# hub.net
KiCad netlist of a schematic drawn in EAGLE
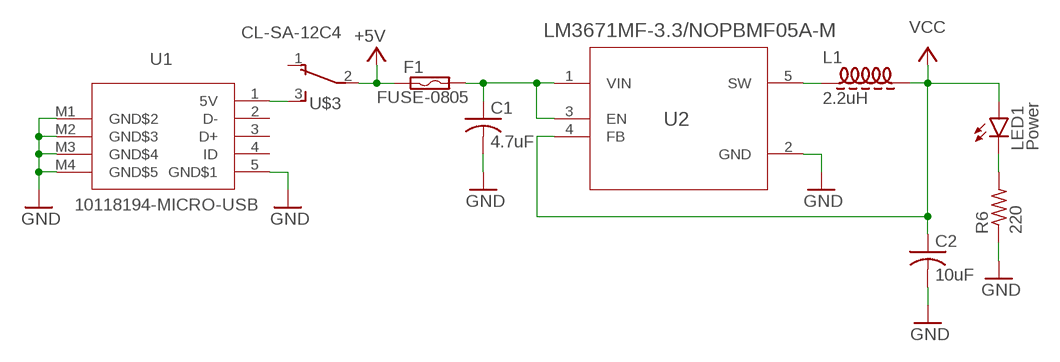
[diagram p0: schematic, sheet 1]
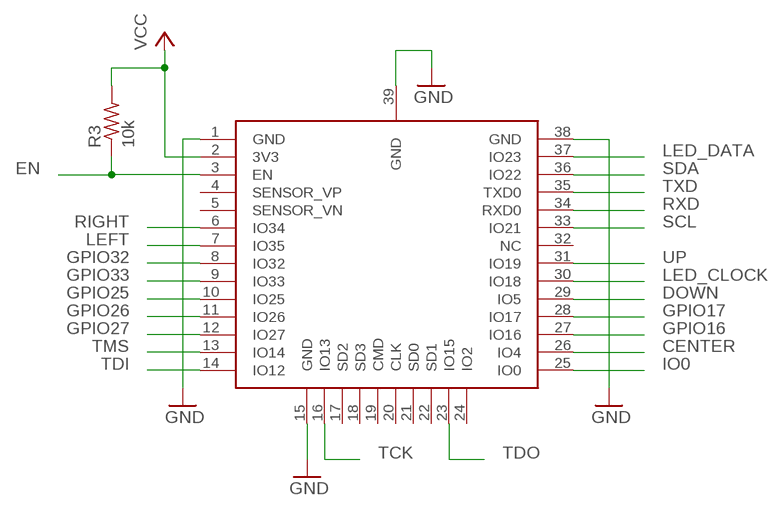
[diagram p1: schematic, sheet 2]
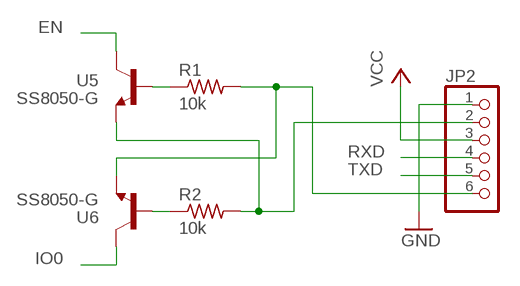
[diagram p2: schematic, sheet 3]
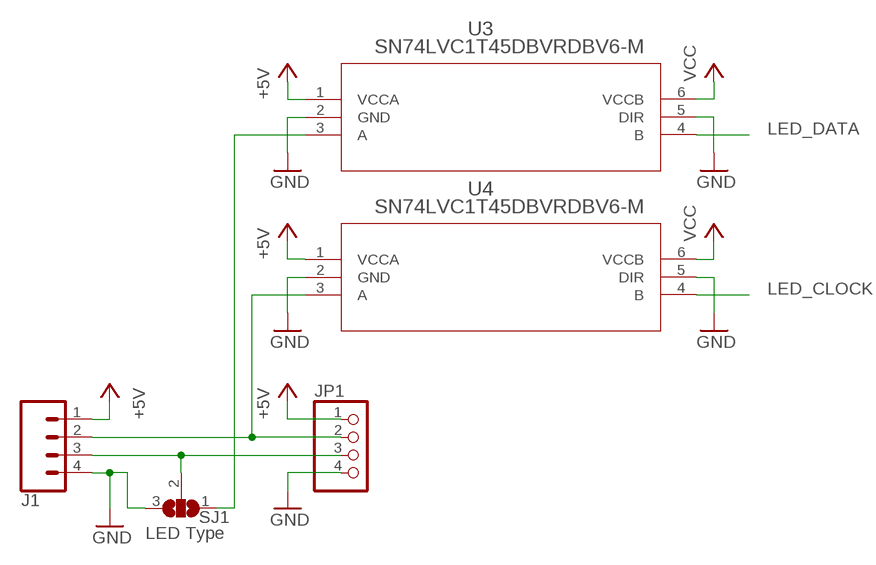
[diagram p3: schematic, sheet 4]
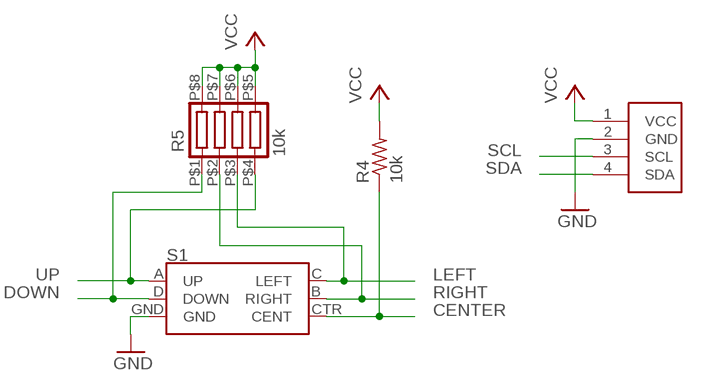
[diagram p4: schematic, sheet 5]
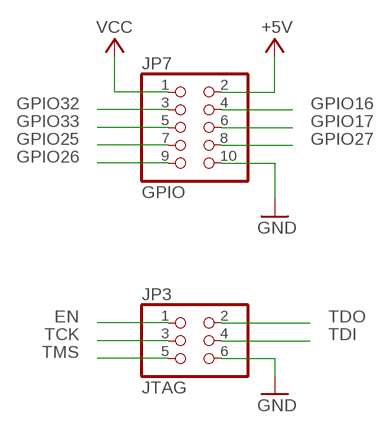
[diagram p5: schematic, sheet 6]

(export (version "E")
  (design (tool "Eeschema 10.0.6"))
  (components
    (comp (ref "R3")
      (value "10k")
      (footprint "eagle-import:R0805")
      (libsource (lib "eagle-import") (part "R-US_R0805"))
    )
    (comp (ref "U$2")
      (value "ESP32-WROOM-32D")
      (footprint "eagle-import:ESP32-WROOM-32D")
      (libsource (lib "eagle-import") (part "ESP32-WROOM-32D"))
    )
    (comp (ref "C1")
      (value "4.7uF")
      (footprint "eagle-import:C0805")
      (libsource (lib "eagle-import") (part "C-USC0805"))
    )
    (comp (ref "C2")
      (value "10uF")
      (footprint "eagle-import:C0805")
      (libsource (lib "eagle-import") (part "C-USC0805"))
    )
    (comp (ref "F1")
      (value "FUSE-0805")
      (footprint "eagle-import:R0805")
      (libsource (lib "eagle-import") (part "FUSE-0805"))
    )
    (comp (ref "L1")
      (value "2.2uH")
      (footprint "eagle-import:R0805")
      (libsource (lib "eagle-import") (part "IND-0805"))
    )
    (comp (ref "LED1")
      (value "Power")
      (footprint "eagle-import:CHIPLED_0805")
      (libsource (lib "eagle-import") (part "LEDCHIPLED_0805"))
    )
    (comp (ref "R6")
      (value "220")
      (footprint "eagle-import:R0805")
      (libsource (lib "eagle-import") (part "R-US_R0805"))
    )
    (comp (ref "U$3")
      (value "CL-SA-12C4")
      (footprint "eagle-import:CL-SA-12C4")
      (libsource (lib "eagle-import") (part "CL-SA-12C4"))
    )
    (comp (ref "U1")
      (value "10118194-MICRO-USB")
      (footprint "eagle-import:10118194-MICRO-USB")
      (libsource (lib "eagle-import") (part "10118194-MICRO-USB"))
    )
    (comp (ref "U2")
      (value "LM3671MF-3.3/NOPBMF05A-M")
      (footprint "eagle-import:MF05A-M")
      (fields (field (name "MANUFACTURER_PART_NUMBER") "LM3671MF3.3NOPB"))
      (libsource (lib "eagle-import") (part "LM3671MF-3.3/NOPBMF05A-M"))
    )
    (comp (ref "JP3")
      (value "JTAG")
      (footprint "eagle-import:2X03")
      (libsource (lib "eagle-import") (part "PINHD-2X3"))
    )
    (comp (ref "JP7")
      (value "GPIO")
      (footprint "eagle-import:2X05")
      (libsource (lib "eagle-import") (part "PINHD-2X5"))
    )
    (comp (ref "J1")
      (value "CONN_04SCREW")
      (footprint "eagle-import:SCREWTERMINAL-3.5MM-4")
      (libsource (lib "eagle-import") (part "CONN_04SCREW"))
    )
    (comp (ref "JP1")
      (value "PINHD-1X4")
      (footprint "eagle-import:1X04")
      (libsource (lib "eagle-import") (part "PINHD-1X4"))
    )
    (comp (ref "SJ1")
      (value "LED Type")
      (footprint "eagle-import:SJ_2")
      (libsource (lib "eagle-import") (part "SJ2W"))
    )
    (comp (ref "U3")
      (value "SN74LVC1T45DBVRDBV6-M")
      (footprint "eagle-import:DBV6-M")
      (fields (field (name "MANUFACTURER_PART_NUMBER") "SN74LVC1T45DBVR"))
      (libsource (lib "eagle-import") (part "SN74LVC1T45DBVRDBV6-M"))
    )
    (comp (ref "U4")
      (value "SN74LVC1T45DBVRDBV6-M")
      (footprint "eagle-import:DBV6-M")
      (fields (field (name "MANUFACTURER_PART_NUMBER") "SN74LVC1T45DBVR"))
      (libsource (lib "eagle-import") (part "SN74LVC1T45DBVRDBV6-M"))
    )
    (comp (ref "JP2")
      (value "FTDI")
      (footprint "eagle-import:1X06")
      (libsource (lib "eagle-import") (part "PINHD-1X6"))
    )
    (comp (ref "R1")
      (value "10k")
      (footprint "eagle-import:R0805")
      (libsource (lib "eagle-import") (part "R-US_R0805"))
    )
    (comp (ref "R2")
      (value "10k")
      (footprint "eagle-import:R0805")
      (libsource (lib "eagle-import") (part "R-US_R0805"))
    )
    (comp (ref "U5")
      (value "SS8050-G")
      (footprint "eagle-import:SC-59")
      (libsource (lib "eagle-import") (part "SS8050-G"))
    )
    (comp (ref "U6")
      (value "SS8050-G")
      (footprint "eagle-import:SC-59")
      (libsource (lib "eagle-import") (part "SS8050-G"))
    )
    (comp (ref "R4")
      (value "10k")
      (footprint "eagle-import:R0805")
      (libsource (lib "eagle-import") (part "R-US_R0805"))
    )
    (comp (ref "R5")
      (value "10k")
      (footprint "eagle-import:2012-4N-CONCAVE")
      (libsource (lib "eagle-import") (part "744C083"))
    )
    (comp (ref "S1")
      (value "JOYSTICK_MINI")
      (footprint "eagle-import:JOYSTICK_MINI")
      (libsource (lib "eagle-import") (part "JOYSTICK_MINI"))
    )
    (comp (ref "U$5")
      (value "SSD1306-OLED")
      (footprint "eagle-import:SSD1306-OLED")
      (libsource (lib "eagle-import") (part "SSD1306-OLED"))
    )
  )
  (nets
    (net (code "1") (name "+5V") (class "Default")
      (node (ref "F1") (pin "1") (pinfunction "1_1") (pintype "passive"))
      (node (ref "J1") (pin "1") (pinfunction "1_1") (pintype "passive"))
      (node (ref "JP1") (pin "1") (pinfunction "1_1") (pintype "passive"))
      (node (ref "JP7") (pin "2") (pinfunction "2_2") (pintype "passive"))
      (node (ref "U$3") (pin "2") (pinfunction "2_2") (pintype "passive"))
      (node (ref "U3") (pin "1") (pinfunction "VCCA_1") (pintype "power_in"))
      (node (ref "U4") (pin "1") (pinfunction "VCCA_1") (pintype "power_in"))
    )
    (net (code "2") (name "CENTER") (class "Default")
      (node (ref "R4") (pin "1") (pinfunction "1_1") (pintype "passive"))
      (node (ref "S1") (pin "CTR") (pinfunction "CENT_CTR") (pintype "bidirectional"))
      (node (ref "U$2") (pin "26") (pinfunction "IO4_26") (pintype "bidirectional"))
    )
    (net (code "3") (name "DOWN") (class "Default")
      (node (ref "R5") (pin "P$1") (pinfunction "1_P$1") (pintype "passive"))
      (node (ref "S1") (pin "D") (pinfunction "DOWN_D") (pintype "bidirectional"))
      (node (ref "U$2") (pin "29") (pinfunction "IO5_29") (pintype "passive"))
    )
    (net (code "4") (name "EN") (class "Default")
      (node (ref "JP3") (pin "1") (pinfunction "1_1") (pintype "passive"))
      (node (ref "R3") (pin "1") (pinfunction "1_1") (pintype "passive"))
      (node (ref "U$2") (pin "3") (pinfunction "EN_3") (pintype "passive"))
      (node (ref "U5") (pin "3") (pinfunction "C_3") (pintype "passive"))
    )
    (net (code "5") (name "GND") (class "Default")
      (node (ref "C1") (pin "2") (pinfunction "2_2") (pintype "passive"))
      (node (ref "C2") (pin "2") (pinfunction "2_2") (pintype "passive"))
      (node (ref "J1") (pin "4") (pinfunction "4_4") (pintype "passive"))
      (node (ref "JP1") (pin "4") (pinfunction "4_4") (pintype "passive"))
      (node (ref "JP2") (pin "1") (pinfunction "1_1") (pintype "passive"))
      (node (ref "JP3") (pin "6") (pinfunction "6_6") (pintype "passive"))
      (node (ref "JP7") (pin "10") (pinfunction "10_10") (pintype "passive"))
      (node (ref "R6") (pin "1") (pinfunction "1_1") (pintype "passive"))
      (node (ref "S1") (pin "GND") (pinfunction "GND_GND") (pintype "bidirectional"))
      (node (ref "SJ1") (pin "3") (pinfunction "3_3") (pintype "passive"))
      (node (ref "U$2") (pin "1") (pinfunction "GND_1") (pintype "passive"))
      (node (ref "U$2") (pin "15") (pinfunction "GND_15") (pintype "passive"))
      (node (ref "U$2") (pin "38") (pinfunction "GND_38") (pintype "passive"))
      (node (ref "U$2") (pin "39") (pinfunction "GND_39") (pintype "bidirectional"))
      (node (ref "U$5") (pin "2") (pinfunction "GND_2") (pintype "power_in"))
      (node (ref "U1") (pin "5") (pinfunction "GND$1_5") (pintype "bidirectional"))
      (node (ref "U1") (pin "M1") (pinfunction "GND$2_M1") (pintype "passive"))
      (node (ref "U1") (pin "M2") (pinfunction "GND$3_M2") (pintype "passive"))
      (node (ref "U1") (pin "M3") (pinfunction "GND$4_M3") (pintype "passive"))
      (node (ref "U1") (pin "M4") (pinfunction "GND$5_M4") (pintype "passive"))
      (node (ref "U2") (pin "2") (pinfunction "GND_2") (pintype "passive"))
      (node (ref "U3") (pin "2") (pinfunction "GND_2") (pintype "power_in"))
      (node (ref "U3") (pin "5") (pinfunction "DIR_5") (pintype "input"))
      (node (ref "U4") (pin "2") (pinfunction "GND_2") (pintype "power_in"))
      (node (ref "U4") (pin "5") (pinfunction "DIR_5") (pintype "input"))
    )
    (net (code "6") (name "GPIO16") (class "Default")
      (node (ref "JP7") (pin "4") (pinfunction "4_4") (pintype "passive"))
      (node (ref "U$2") (pin "27") (pinfunction "IO16_27") (pintype "bidirectional"))
    )
    (net (code "7") (name "GPIO17") (class "Default")
      (node (ref "JP7") (pin "6") (pinfunction "6_6") (pintype "passive"))
      (node (ref "U$2") (pin "28") (pinfunction "IO17_28") (pintype "passive"))
    )
    (net (code "8") (name "GPIO25") (class "Default")
      (node (ref "JP7") (pin "7") (pinfunction "7_7") (pintype "passive"))
      (node (ref "U$2") (pin "10") (pinfunction "IO25_10") (pintype "passive"))
    )
    (net (code "9") (name "GPIO26") (class "Default")
      (node (ref "JP7") (pin "9") (pinfunction "9_9") (pintype "passive"))
      (node (ref "U$2") (pin "11") (pinfunction "IO26_11") (pintype "passive"))
    )
    (net (code "10") (name "GPIO27") (class "Default")
      (node (ref "JP7") (pin "8") (pinfunction "8_8") (pintype "passive"))
      (node (ref "U$2") (pin "12") (pinfunction "IO27_12") (pintype "bidirectional"))
    )
    (net (code "11") (name "GPIO32") (class "Default")
      (node (ref "JP7") (pin "3") (pinfunction "3_3") (pintype "passive"))
      (node (ref "U$2") (pin "8") (pinfunction "IO32_8") (pintype "passive"))
    )
    (net (code "12") (name "GPIO33") (class "Default")
      (node (ref "JP7") (pin "5") (pinfunction "5_5") (pintype "passive"))
      (node (ref "U$2") (pin "9") (pinfunction "IO33_9") (pintype "passive"))
    )
    (net (code "13") (name "IO0") (class "Default")
      (node (ref "U$2") (pin "25") (pinfunction "IO0_25") (pintype "bidirectional"))
      (node (ref "U6") (pin "3") (pinfunction "C_3") (pintype "passive"))
    )
    (net (code "14") (name "LED_CLOCK") (class "Default")
      (node (ref "U$2") (pin "30") (pinfunction "IO18_30") (pintype "passive"))
      (node (ref "U4") (pin "4") (pinfunction "B_4") (pintype "input"))
    )
    (net (code "15") (name "LED_DATA") (class "Default")
      (node (ref "U$2") (pin "37") (pinfunction "IO23_37") (pintype "passive"))
      (node (ref "U3") (pin "4") (pinfunction "B_4") (pintype "input"))
    )
    (net (code "16") (name "LEFT") (class "Default")
      (node (ref "R5") (pin "P$3") (pinfunction "3_P$3") (pintype "passive"))
      (node (ref "S1") (pin "C") (pinfunction "LEFT_C") (pintype "bidirectional"))
      (node (ref "U$2") (pin "7") (pinfunction "IO35_7") (pintype "passive"))
    )
    (net (code "17") (name "Net-(J1-Pad3)") (class "Default")
      (node (ref "J1") (pin "3") (pinfunction "3_3") (pintype "passive"))
      (node (ref "JP1") (pin "3") (pinfunction "3_3") (pintype "passive"))
      (node (ref "SJ1") (pin "2") (pinfunction "2_2") (pintype "passive"))
    )
    (net (code "18") (name "Net-(LED1-PadC)") (class "Default")
      (node (ref "LED1") (pin "C") (pinfunction "C_C") (pintype "passive"))
      (node (ref "R6") (pin "2") (pinfunction "2_2") (pintype "passive"))
    )
    (net (code "19") (name "Net-(U1-5V)") (class "Default")
      (node (ref "U$3") (pin "3") (pinfunction "3_3") (pintype "passive"))
      (node (ref "U1") (pin "1") (pinfunction "5V_1") (pintype "bidirectional"))
    )
    (net (code "20") (name "Net-(U2-EN)") (class "Default")
      (node (ref "C1") (pin "1") (pinfunction "1_1") (pintype "passive"))
      (node (ref "F1") (pin "2") (pinfunction "2_2") (pintype "passive"))
      (node (ref "U2") (pin "1") (pinfunction "VIN_1") (pintype "input"))
      (node (ref "U2") (pin "3") (pinfunction "EN_3") (pintype "passive"))
    )
    (net (code "21") (name "Net-(U2-SW)") (class "Default")
      (node (ref "L1") (pin "1") (pinfunction "1_1") (pintype "passive"))
      (node (ref "U2") (pin "5") (pinfunction "SW_5") (pintype "output"))
    )
    (net (code "22") (name "Net-(U3-A)") (class "Default")
      (node (ref "SJ1") (pin "1") (pinfunction "1_1") (pintype "passive"))
      (node (ref "U3") (pin "3") (pinfunction "A_3") (pintype "input"))
    )
    (net (code "23") (name "Net-(U4-A)") (class "Default")
      (node (ref "J1") (pin "2") (pinfunction "2_2") (pintype "passive"))
      (node (ref "JP1") (pin "2") (pinfunction "2_2") (pintype "passive"))
      (node (ref "U4") (pin "3") (pinfunction "A_3") (pintype "input"))
    )
    (net (code "24") (name "Net-(U5-B)") (class "Default")
      (node (ref "R1") (pin "1") (pinfunction "1_1") (pintype "passive"))
      (node (ref "U5") (pin "1") (pinfunction "B_1") (pintype "passive"))
    )
    (net (code "25") (name "Net-(U5-E)") (class "Default")
      (node (ref "JP2") (pin "2") (pinfunction "2_2") (pintype "passive"))
      (node (ref "R2") (pin "2") (pinfunction "2_2") (pintype "passive"))
      (node (ref "U5") (pin "2") (pinfunction "E_2") (pintype "passive"))
    )
    (net (code "26") (name "Net-(U6-B)") (class "Default")
      (node (ref "R2") (pin "1") (pinfunction "1_1") (pintype "passive"))
      (node (ref "U6") (pin "1") (pinfunction "B_1") (pintype "passive"))
    )
    (net (code "27") (name "Net-(U6-E)") (class "Default")
      (node (ref "JP2") (pin "6") (pinfunction "6_6") (pintype "passive"))
      (node (ref "R1") (pin "2") (pinfunction "2_2") (pintype "passive"))
      (node (ref "U6") (pin "2") (pinfunction "E_2") (pintype "passive"))
    )
    (net (code "28") (name "RIGHT") (class "Default")
      (node (ref "R5") (pin "P$2") (pinfunction "2_P$2") (pintype "passive"))
      (node (ref "S1") (pin "B") (pinfunction "RIGHT_B") (pintype "bidirectional"))
      (node (ref "U$2") (pin "6") (pinfunction "IO34_6") (pintype "passive"))
    )
    (net (code "29") (name "RXD") (class "Default")
      (node (ref "JP2") (pin "4") (pinfunction "4_4") (pintype "passive"))
      (node (ref "U$2") (pin "34") (pinfunction "RXD0_34") (pintype "passive"))
    )
    (net (code "30") (name "SCL") (class "Default")
      (node (ref "U$2") (pin "33") (pinfunction "IO21_33") (pintype "passive"))
      (node (ref "U$5") (pin "3") (pinfunction "SCL_3") (pintype "passive"))
    )
    (net (code "31") (name "SDA") (class "Default")
      (node (ref "U$2") (pin "36") (pinfunction "IO22_36") (pintype "passive"))
      (node (ref "U$5") (pin "4") (pinfunction "SDA_4") (pintype "passive"))
    )
    (net (code "32") (name "TCK") (class "Default")
      (node (ref "JP3") (pin "3") (pinfunction "3_3") (pintype "passive"))
      (node (ref "U$2") (pin "16") (pinfunction "IO13_16") (pintype "passive"))
    )
    (net (code "33") (name "TDI") (class "Default")
      (node (ref "JP3") (pin "4") (pinfunction "4_4") (pintype "passive"))
      (node (ref "U$2") (pin "14") (pinfunction "IO12_14") (pintype "bidirectional"))
    )
    (net (code "34") (name "TDO") (class "Default")
      (node (ref "JP3") (pin "2") (pinfunction "2_2") (pintype "passive"))
      (node (ref "U$2") (pin "23") (pinfunction "IO15_23") (pintype "passive"))
    )
    (net (code "35") (name "TMS") (class "Default")
      (node (ref "JP3") (pin "5") (pinfunction "5_5") (pintype "passive"))
      (node (ref "U$2") (pin "13") (pinfunction "IO14_13") (pintype "bidirectional"))
    )
    (net (code "36") (name "TXD") (class "Default")
      (node (ref "JP2") (pin "5") (pinfunction "5_5") (pintype "passive"))
      (node (ref "U$2") (pin "35") (pinfunction "TXD0_35") (pintype "passive"))
    )
    (net (code "37") (name "UP") (class "Default")
      (node (ref "R5") (pin "P$4") (pinfunction "4_P$4") (pintype "passive"))
      (node (ref "S1") (pin "A") (pinfunction "UP_A") (pintype "bidirectional"))
      (node (ref "U$2") (pin "31") (pinfunction "IO19_31") (pintype "passive"))
    )
    (net (code "38") (name "VCC") (class "Default")
      (node (ref "C2") (pin "1") (pinfunction "1_1") (pintype "passive"))
      (node (ref "JP2") (pin "3") (pinfunction "3_3") (pintype "passive"))
      (node (ref "JP7") (pin "1") (pinfunction "1_1") (pintype "passive"))
      (node (ref "L1") (pin "2") (pinfunction "2_2") (pintype "passive"))
      (node (ref "LED1") (pin "A") (pinfunction "A_A") (pintype "passive"))
      (node (ref "R3") (pin "2") (pinfunction "2_2") (pintype "passive"))
      (node (ref "R4") (pin "2") (pinfunction "2_2") (pintype "passive"))
      (node (ref "R5") (pin "P$5") (pinfunction "5_P$5") (pintype "passive"))
      (node (ref "R5") (pin "P$6") (pinfunction "6_P$6") (pintype "passive"))
      (node (ref "R5") (pin "P$7") (pinfunction "7_P$7") (pintype "passive"))
      (node (ref "R5") (pin "P$8") (pinfunction "8_P$8") (pintype "passive"))
      (node (ref "U$2") (pin "2") (pinfunction "3V3_2") (pintype "passive"))
      (node (ref "U$5") (pin "1") (pinfunction "VCC_1") (pintype "power_in"))
      (node (ref "U2") (pin "4") (pinfunction "FB_4") (pintype "passive"))
      (node (ref "U3") (pin "6") (pinfunction "VCCB_6") (pintype "power_in"))
      (node (ref "U4") (pin "6") (pinfunction "VCCB_6") (pintype "power_in"))
    )
    (net (code "39") (name "unconnected-(U$2-CLK-Pad20)") (class "Default")
      (node (ref "U$2") (pin "20") (pinfunction "CLK_20") (pintype "no_connect"))
    )
    (net (code "40") (name "unconnected-(U$2-CMD-Pad19)") (class "Default")
      (node (ref "U$2") (pin "19") (pinfunction "CMD_19") (pintype "no_connect"))
    )
    (net (code "41") (name "unconnected-(U$2-IO2-Pad24)") (class "Default")
      (node (ref "U$2") (pin "24") (pinfunction "IO2_24") (pintype "passive"))
    )
    (net (code "42") (name "unconnected-(U$2-NC-Pad32)") (class "Default")
      (node (ref "U$2") (pin "32") (pinfunction "NC_32") (pintype "no_connect"))
    )
    (net (code "43") (name "unconnected-(U$2-SD0-Pad21)") (class "Default")
      (node (ref "U$2") (pin "21") (pinfunction "SD0_21") (pintype "no_connect"))
    )
    (net (code "44") (name "unconnected-(U$2-SD1-Pad22)") (class "Default")
      (node (ref "U$2") (pin "22") (pinfunction "SD1_22") (pintype "no_connect"))
    )
    (net (code "45") (name "unconnected-(U$2-SD2-Pad17)") (class "Default")
      (node (ref "U$2") (pin "17") (pinfunction "SD2_17") (pintype "no_connect"))
    )
    (net (code "46") (name "unconnected-(U$2-SD3-Pad18)") (class "Default")
      (node (ref "U$2") (pin "18") (pinfunction "SD3_18") (pintype "no_connect"))
    )
    (net (code "47") (name "unconnected-(U$2-SENSOR_VN-Pad5)") (class "Default")
      (node (ref "U$2") (pin "5") (pinfunction "SENSOR_VN_5") (pintype "passive"))
    )
    (net (code "48") (name "unconnected-(U$2-SENSOR_VP-Pad4)") (class "Default")
      (node (ref "U$2") (pin "4") (pinfunction "SENSOR_VP_4") (pintype "passive"))
    )
    (net (code "49") (name "unconnected-(U$3-Pad1)") (class "Default")
      (node (ref "U$3") (pin "1") (pinfunction "1_1") (pintype "passive"))
    )
    (net (code "50") (name "unconnected-(U1-D+-Pad3)") (class "Default")
      (node (ref "U1") (pin "3") (pinfunction "D+_3") (pintype "bidirectional"))
    )
    (net (code "51") (name "unconnected-(U1-D--Pad2)") (class "Default")
      (node (ref "U1") (pin "2") (pinfunction "D-_2") (pintype "bidirectional"))
    )
    (net (code "52") (name "unconnected-(U1-ID-Pad4)") (class "Default")
      (node (ref "U1") (pin "4") (pinfunction "ID_4") (pintype "bidirectional"))
    )
  )
)
